# AD8317.net
KiCad netlist of a schematic drawn in Altium Designer
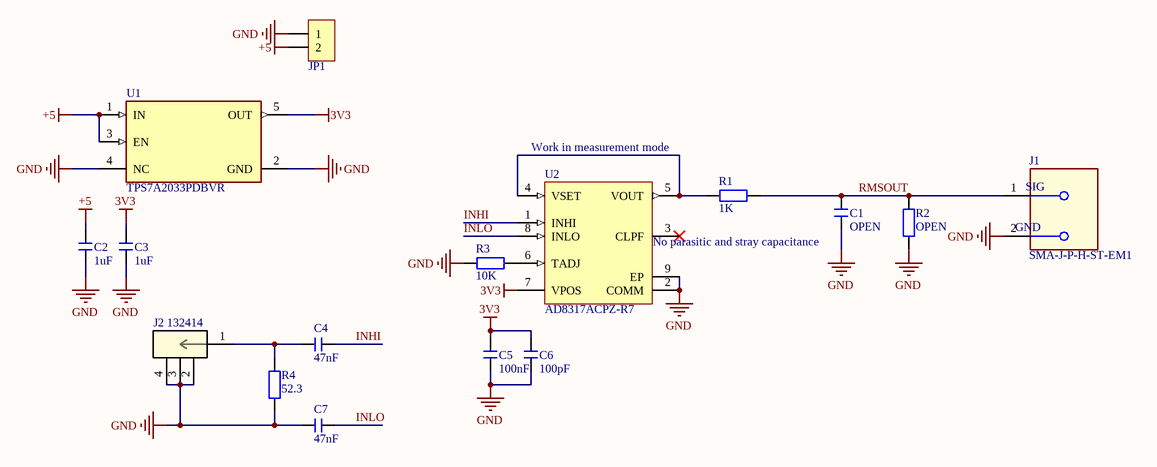
[diagram p0: AD8317.SchDoc]

(export (version "E")
  (design (tool "Eeschema 10.0.6"))
  (components
    (comp (ref "C1")
      (value "OPEN")
      (footprint "C 0402_L")
      (description "贴片电容")
      (libsource (lib "01 - 电容-电阻-电感") (part "C"))
    )
    (comp (ref "C2")
      (value "1uF")
      (footprint "C 0402_L")
      (description "贴片电容")
      (libsource (lib "01 - 电容-电阻-电感") (part "C"))
    )
    (comp (ref "C3")
      (value "1uF")
      (footprint "C 0402_L")
      (description "贴片电容")
      (libsource (lib "01 - 电容-电阻-电感") (part "C"))
    )
    (comp (ref "C4")
      (value "47nF")
      (footprint "C 0402_L")
      (description "贴片电容")
      (libsource (lib "01 - 电容-电阻-电感") (part "C"))
    )
    (comp (ref "C5")
      (value "100nF")
      (footprint "C 0402_L")
      (description "贴片电容")
      (libsource (lib "01 - 电容-电阻-电感") (part "C"))
    )
    (comp (ref "C6")
      (value "100pF")
      (footprint "C 0402_L")
      (description "贴片电容")
      (libsource (lib "01 - 电容-电阻-电感") (part "C"))
    )
    (comp (ref "C7")
      (value "47nF")
      (footprint "C 0402_L")
      (description "贴片电容")
      (libsource (lib "01 - 电容-电阻-电感") (part "C"))
    )
    (comp (ref "J1")
      (value "SMA-J-P-H-ST-EM1")
      (footprint "FP-SMA-J-P-H-ST-EM1-MFG")
      (description "CONN SMA JACK STR 50OHM EDGE MNT")
      (libsource (lib "卧式SMA") (part "CMP-02754-000006-1"))
    )
    (comp (ref "J2")
      (value "132414")
      (footprint "CONN_132414_AMP")
      (description "No Description Available")
      (fields (field (name "COPYRIGHT") "Copyright (C) 2022 Ultra Librarian. All rights reserved."))
      (libsource (lib "细针大偏脚SMA(用这个)") (part "132414"))
    )
    (comp (ref "JP1")
      (value "HDR-1X2")
      (footprint "KF2510-LI-2P")
      (description "2P接插件")
      (libsource (lib "18 - 接插件-脚距2.54mm (100mil) ") (part "Header 2"))
    )
    (comp (ref "R1")
      (value "1K")
      (footprint "R 0402_L")
      (description "贴片电阻")
      (libsource (lib "01 - 电容-电阻-电感") (part "R"))
    )
    (comp (ref "R2")
      (value "OPEN")
      (footprint "R 0402_L")
      (description "贴片电阻")
      (libsource (lib "01 - 电容-电阻-电感") (part "R"))
    )
    (comp (ref "R3")
      (value "10K")
      (footprint "R 0402_L")
      (description "贴片电阻")
      (libsource (lib "01 - 电容-电阻-电感") (part "R"))
    )
    (comp (ref "R4")
      (value "52.3")
      (footprint "R 0402_L")
      (description "贴片电阻")
      (libsource (lib "01 - 电容-电阻-电感") (part "R"))
    )
    (comp (ref "U1")
      (value "TPS7A2033PDBVR")
      (footprint "FP-DBV0005A-IPC_C")
      (libsource (lib "TPS7A2050DBVR") (part "TPS7A2050"))
    )
    (comp (ref "U2")
      (value "AD8317ACPZ-R7")
      (footprint "ADI-CP-8-1_L")
      (description "1 MHz to 10 GHz, 55 dB Log Detector/Controller, 6ns Response Time, CP-8-1, Pb-Free, 3000 Reel")
      (libsource (lib "AD8317ACPZ") (part "CMP-0284-00065-1"))
    )
  )
  (nets
    (net (code "1") (name "+5") (class "Default")
      (node (ref "C2") (pin "1") (pinfunction "1_1") (pintype "passive"))
      (node (ref "JP1") (pin "2") (pinfunction "2_2") (pintype "passive"))
      (node (ref "U1") (pin "1") (pinfunction "IN_1") (pintype "input"))
      (node (ref "U1") (pin "3") (pinfunction "EN_3") (pintype "input"))
    )
    (net (code "2") (name "/INHI") (class "Default")
      (node (ref "C4") (pin "2") (pinfunction "2_2") (pintype "passive"))
      (node (ref "U2") (pin "1") (pinfunction "INHI_1") (pintype "input"))
    )
    (net (code "3") (name "/INLO") (class "Default")
      (node (ref "C7") (pin "2") (pinfunction "2_2") (pintype "passive"))
      (node (ref "U2") (pin "8") (pinfunction "INLO_8") (pintype "input"))
    )
    (net (code "4") (name "/RMSOUT") (class "Default")
      (node (ref "C1") (pin "2") (pinfunction "2_2") (pintype "passive"))
      (node (ref "J1") (pin "1") (pinfunction "1_1") (pintype "passive"))
      (node (ref "R1") (pin "1") (pinfunction "1_1") (pintype "passive"))
      (node (ref "R2") (pin "2") (pinfunction "2_2") (pintype "passive"))
    )
    (net (code "5") (name "3V3") (class "Default")
      (node (ref "C3") (pin "2") (pinfunction "2_2") (pintype "passive"))
      (node (ref "C5") (pin "2") (pinfunction "2_2") (pintype "passive"))
      (node (ref "C6") (pin "2") (pinfunction "2_2") (pintype "passive"))
      (node (ref "U1") (pin "5") (pinfunction "OUT_5") (pintype "output"))
      (node (ref "U2") (pin "7") (pinfunction "VPOS_7") (pintype "power_in"))
    )
    (net (code "6") (name "GND") (class "Default")
      (node (ref "C1") (pin "1") (pinfunction "1_1") (pintype "passive"))
      (node (ref "C2") (pin "2") (pinfunction "2_2") (pintype "passive"))
      (node (ref "C3") (pin "1") (pinfunction "1_1") (pintype "passive"))
      (node (ref "C5") (pin "1") (pinfunction "1_1") (pintype "passive"))
      (node (ref "C6") (pin "1") (pinfunction "1_1") (pintype "passive"))
      (node (ref "C7") (pin "1") (pinfunction "1_1") (pintype "passive"))
      (node (ref "J1") (pin "2") (pinfunction "MNT_1_2") (pintype "passive"))
      (node (ref "J2") (pin "2") (pinfunction "2_2") (pintype "passive"))
      (node (ref "J2") (pin "3") (pinfunction "3_3") (pintype "passive"))
      (node (ref "J2") (pin "4") (pinfunction "4_4") (pintype "passive"))
      (node (ref "JP1") (pin "1") (pinfunction "1_1") (pintype "passive"))
      (node (ref "R2") (pin "1") (pinfunction "1_1") (pintype "passive"))
      (node (ref "R3") (pin "2") (pinfunction "2_2") (pintype "passive"))
      (node (ref "R4") (pin "1") (pinfunction "1_1") (pintype "passive"))
      (node (ref "U1") (pin "2") (pinfunction "GND_2") (pintype "power_in"))
      (node (ref "U1") (pin "4") (pinfunction "NC_4") (pintype "passive"))
      (node (ref "U2") (pin "2") (pinfunction "COMM_2") (pintype "power_in"))
      (node (ref "U2") (pin "9") (pinfunction "EP_9") (pintype "power_in"))
    )
    (net (code "7") (name "Net-(C4-Pad1)") (class "Default")
      (node (ref "C4") (pin "1") (pinfunction "1_1") (pintype "passive"))
      (node (ref "J2") (pin "1") (pinfunction "1_1") (pintype "passive"))
      (node (ref "R4") (pin "2") (pinfunction "2_2") (pintype "passive"))
    )
    (net (code "8") (name "Net-(U2-TADJ)") (class "Default")
      (node (ref "R3") (pin "1") (pinfunction "1_1") (pintype "passive"))
      (node (ref "U2") (pin "6") (pinfunction "TADJ_6") (pintype "input"))
    )
    (net (code "9") (name "Net-(U2-VOUT)") (class "Default")
      (node (ref "R1") (pin "2") (pinfunction "2_2") (pintype "passive"))
      (node (ref "U2") (pin "4") (pinfunction "VSET_4") (pintype "input"))
      (node (ref "U2") (pin "5") (pinfunction "VOUT_5") (pintype "output"))
    )
    (net (code "10") (name "unconnected-(U2-CLPF-Pad3)") (class "Default")
      (node (ref "U2") (pin "3") (pinfunction "CLPF_3") (pintype "passive+no_connect"))
    )
  )
)
